# SDCI_Converter.net
KiCad netlist of a schematic drawn in Altium Designer
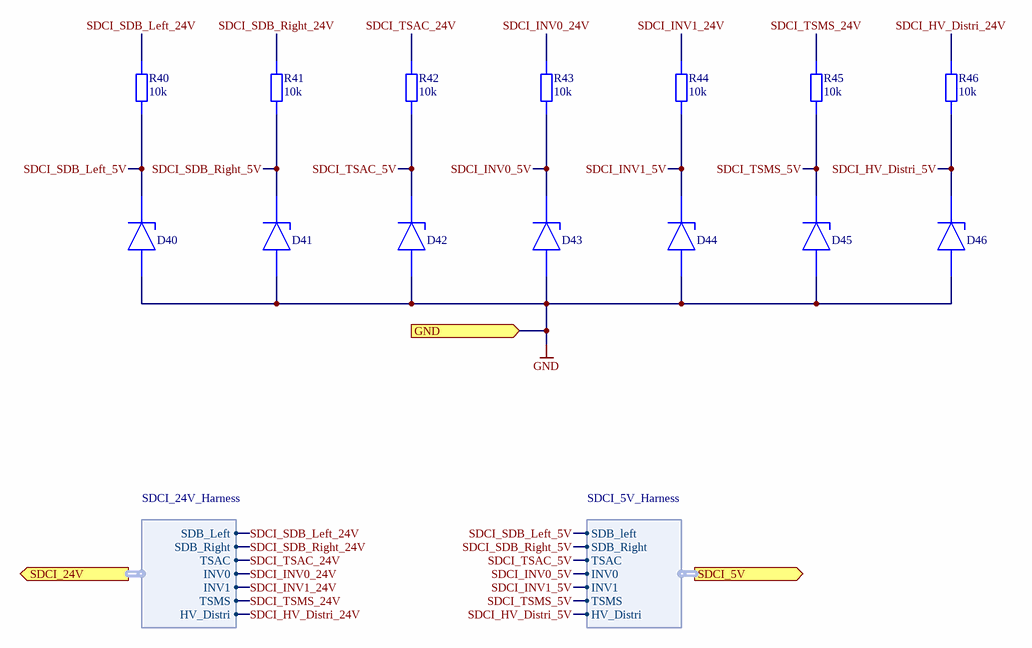
[diagram p0: SDCI_Converter.SchDoc]

(export (version "E")
  (design (tool "Eeschema 10.0.6"))
  (components
    (comp (ref "D40")
      (value "MM3Z4V7T1G")
      (footprint "SOD-323-2")
      (description "onsemi MM3Z4V7T1G\r\nZ-Diode, 4,7V")
      (libsource (lib "libNico") (part "MM3Z4V7T1G"))
    )
    (comp (ref "D41")
      (value "MM3Z4V7T1G")
      (footprint "SOD-323-2")
      (description "onsemi MM3Z4V7T1G\r\nZ-Diode, 4,7V")
      (libsource (lib "libNico") (part "MM3Z4V7T1G"))
    )
    (comp (ref "D42")
      (value "MM3Z4V7T1G")
      (footprint "SOD-323-2")
      (description "onsemi MM3Z4V7T1G\r\nZ-Diode, 4,7V")
      (libsource (lib "libNico") (part "MM3Z4V7T1G"))
    )
    (comp (ref "D43")
      (value "MM3Z4V7T1G")
      (footprint "SOD-323-2")
      (description "onsemi MM3Z4V7T1G\r\nZ-Diode, 4,7V")
      (libsource (lib "libNico") (part "MM3Z4V7T1G"))
    )
    (comp (ref "D44")
      (value "MM3Z4V7T1G")
      (footprint "SOD-323-2")
      (description "onsemi MM3Z4V7T1G\r\nZ-Diode, 4,7V")
      (libsource (lib "libNico") (part "MM3Z4V7T1G"))
    )
    (comp (ref "D45")
      (value "MM3Z4V7T1G")
      (footprint "SOD-323-2")
      (description "onsemi MM3Z4V7T1G\r\nZ-Diode, 4,7V")
      (libsource (lib "libNico") (part "MM3Z4V7T1G"))
    )
    (comp (ref "D46")
      (value "MM3Z4V7T1G")
      (footprint "SOD-323-2")
      (description "onsemi MM3Z4V7T1G\r\nZ-Diode, 4,7V")
      (libsource (lib "libNico") (part "MM3Z4V7T1G"))
    )
    (comp (ref "R40")
      (value "10k")
      (footprint "STACKPOLE CSR0603")
      (description "Resistor with multiple footprints")
      (fields (field (name "POWER") "0.1W") (field (name "Comment") "SMD Resistor"))
      (libsource (lib "Standardbauteile") (part "SMD Resistor"))
    )
    (comp (ref "R41")
      (value "10k")
      (footprint "STACKPOLE CSR0603")
      (description "Resistor with multiple footprints")
      (fields (field (name "POWER") "0.1W") (field (name "Comment") "SMD Resistor"))
      (libsource (lib "Standardbauteile") (part "SMD Resistor"))
    )
    (comp (ref "R42")
      (value "10k")
      (footprint "STACKPOLE CSR0603")
      (description "Resistor with multiple footprints")
      (fields (field (name "POWER") "0.1W") (field (name "Comment") "SMD Resistor"))
      (libsource (lib "Standardbauteile") (part "SMD Resistor"))
    )
    (comp (ref "R43")
      (value "10k")
      (footprint "STACKPOLE CSR0603")
      (description "Resistor with multiple footprints")
      (fields (field (name "POWER") "0.1W") (field (name "Comment") "SMD Resistor"))
      (libsource (lib "Standardbauteile") (part "SMD Resistor"))
    )
    (comp (ref "R44")
      (value "10k")
      (footprint "STACKPOLE CSR0603")
      (description "Resistor with multiple footprints")
      (fields (field (name "POWER") "0.1W") (field (name "Comment") "SMD Resistor"))
      (libsource (lib "Standardbauteile") (part "SMD Resistor"))
    )
    (comp (ref "R45")
      (value "10k")
      (footprint "STACKPOLE CSR0603")
      (description "Resistor with multiple footprints")
      (fields (field (name "POWER") "0.1W") (field (name "Comment") "SMD Resistor"))
      (libsource (lib "Standardbauteile") (part "SMD Resistor"))
    )
    (comp (ref "R46")
      (value "10k")
      (footprint "STACKPOLE CSR0603")
      (description "Resistor with multiple footprints")
      (fields (field (name "POWER") "0.1W") (field (name "Comment") "SMD Resistor"))
      (libsource (lib "Standardbauteile") (part "SMD Resistor"))
    )
  )
  (nets
    (net (code "3") (name "/SDCI_HV_Distri_5V") (class "Default")
      (node (ref "D46") (pin "1C") (pinfunction "C_1C") (pintype "passive"))
      (node (ref "R46") (pin "1") (pinfunction "1_1") (pintype "passive"))
    )
    (net (code "4") (name "/SDCI_HV_Distri_24V") (class "Default")
      (node (ref "R46") (pin "2") (pinfunction "2_2") (pintype "passive"))
    )
    (net (code "5") (name "/SDCI_INV0_5V") (class "Default")
      (node (ref "D43") (pin "1C") (pinfunction "C_1C") (pintype "passive"))
      (node (ref "R43") (pin "1") (pinfunction "1_1") (pintype "passive"))
    )
    (net (code "6") (name "/SDCI_INV0_24V") (class "Default")
      (node (ref "R43") (pin "2") (pinfunction "2_2") (pintype "passive"))
    )
    (net (code "7") (name "/SDCI_INV1_5V") (class "Default")
      (node (ref "D44") (pin "1C") (pinfunction "C_1C") (pintype "passive"))
      (node (ref "R44") (pin "1") (pinfunction "1_1") (pintype "passive"))
    )
    (net (code "8") (name "/SDCI_INV1_24V") (class "Default")
      (node (ref "R44") (pin "2") (pinfunction "2_2") (pintype "passive"))
    )
    (net (code "9") (name "/SDCI_SDB_Left_5V") (class "Default")
      (node (ref "D40") (pin "1C") (pinfunction "C_1C") (pintype "passive"))
      (node (ref "R40") (pin "1") (pinfunction "1_1") (pintype "passive"))
    )
    (net (code "10") (name "/SDCI_SDB_Left_24V") (class "Default")
      (node (ref "R40") (pin "2") (pinfunction "2_2") (pintype "passive"))
    )
    (net (code "11") (name "/SDCI_SDB_Right_5V") (class "Default")
      (node (ref "D41") (pin "1C") (pinfunction "C_1C") (pintype "passive"))
      (node (ref "R41") (pin "1") (pinfunction "1_1") (pintype "passive"))
    )
    (net (code "12") (name "/SDCI_SDB_Right_24V") (class "Default")
      (node (ref "R41") (pin "2") (pinfunction "2_2") (pintype "passive"))
    )
    (net (code "13") (name "/SDCI_TSAC_5V") (class "Default")
      (node (ref "D42") (pin "1C") (pinfunction "C_1C") (pintype "passive"))
      (node (ref "R42") (pin "1") (pinfunction "1_1") (pintype "passive"))
    )
    (net (code "14") (name "/SDCI_TSAC_24V") (class "Default")
      (node (ref "R42") (pin "2") (pinfunction "2_2") (pintype "passive"))
    )
    (net (code "15") (name "/SDCI_TSMS_5V") (class "Default")
      (node (ref "D45") (pin "1C") (pinfunction "C_1C") (pintype "passive"))
      (node (ref "R45") (pin "1") (pinfunction "1_1") (pintype "passive"))
    )
    (net (code "16") (name "/SDCI_TSMS_24V") (class "Default")
      (node (ref "R45") (pin "2") (pinfunction "2_2") (pintype "passive"))
    )
    (net (code "19") (name "GND") (class "Default")
      (node (ref "D40") (pin "2A") (pinfunction "A_2A") (pintype "passive"))
      (node (ref "D41") (pin "2A") (pinfunction "A_2A") (pintype "passive"))
      (node (ref "D42") (pin "2A") (pinfunction "A_2A") (pintype "passive"))
      (node (ref "D43") (pin "2A") (pinfunction "A_2A") (pintype "passive"))
      (node (ref "D44") (pin "2A") (pinfunction "A_2A") (pintype "passive"))
      (node (ref "D45") (pin "2A") (pinfunction "A_2A") (pintype "passive"))
      (node (ref "D46") (pin "2A") (pinfunction "A_2A") (pintype "passive"))
    )
  )
)
